# ESP-VINDRIKTNING_no_batt.net
KiCad netlist of a schematic drawn in EAGLE
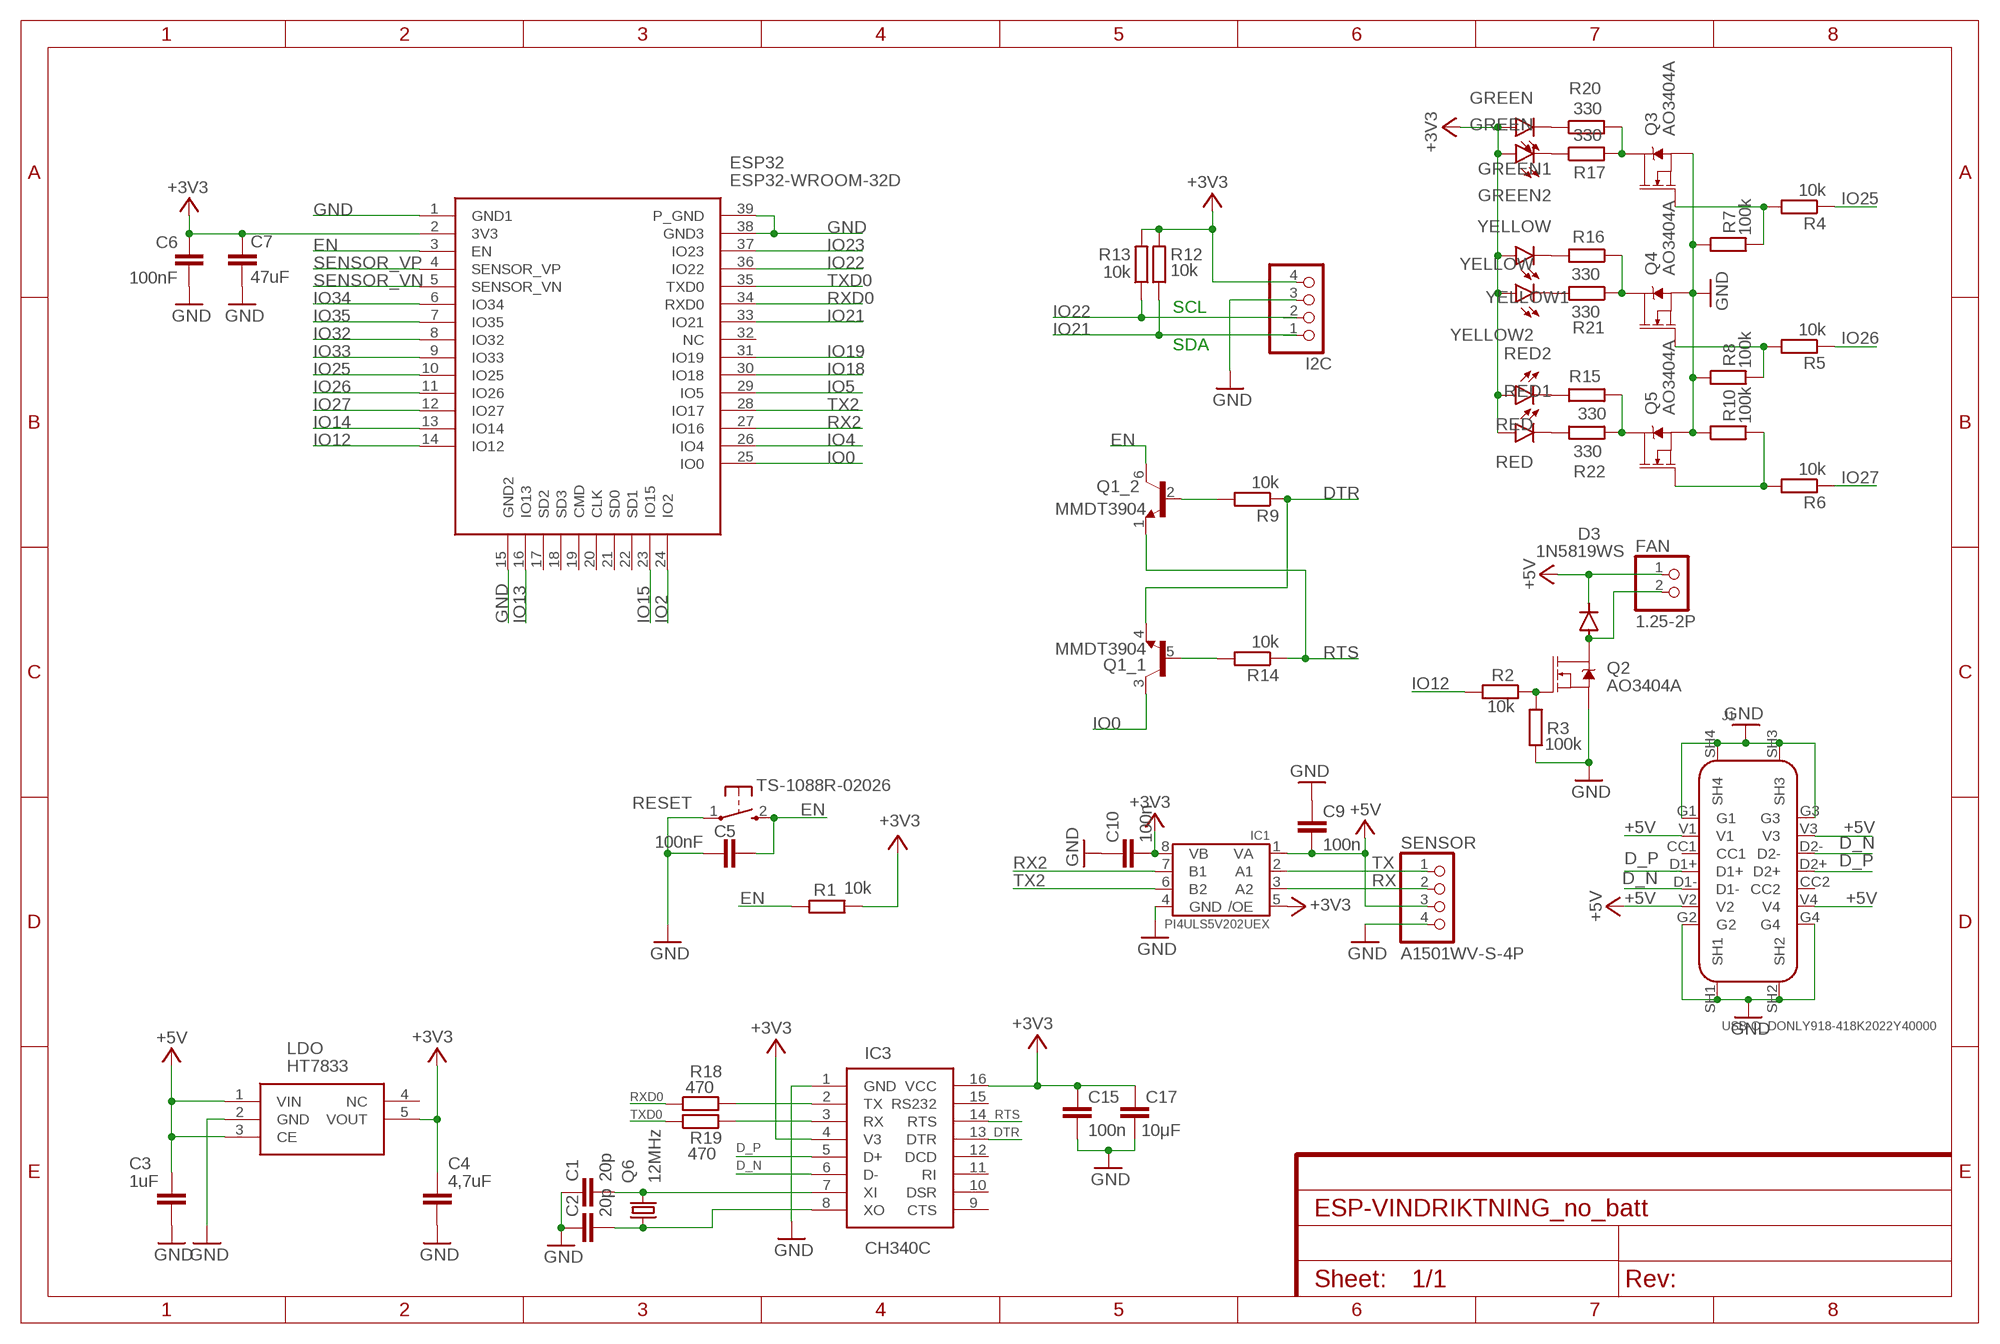
[diagram p0: schematic, sheet 1]

(export (version "E")
  (design (tool "Eeschema 10.0.6"))
  (components
    (comp (ref "C1")
      (value "20p")
      (footprint "eagle-import:C0402")
      (libsource (lib "eagle-import") (part "C-EUC0402"))
    )
    (comp (ref "C2")
      (value "20p")
      (footprint "eagle-import:C0402")
      (libsource (lib "eagle-import") (part "C-EUC0402"))
    )
    (comp (ref "C3")
      (value "1uF")
      (footprint "eagle-import:C0603")
      (libsource (lib "eagle-import") (part "C-EUC0603"))
    )
    (comp (ref "C4")
      (value "4,7uF")
      (footprint "eagle-import:C0603")
      (fields (field (name "LCSC_PART") "C19666"))
      (libsource (lib "eagle-import") (part "C-EUC0603"))
    )
    (comp (ref "C5")
      (value "100nF")
      (footprint "eagle-import:C0402")
      (libsource (lib "eagle-import") (part "C-EUC0402"))
    )
    (comp (ref "C6")
      (value "100nF")
      (footprint "eagle-import:C0603")
      (libsource (lib "eagle-import") (part "C-EUC0603"))
    )
    (comp (ref "C7")
      (value "47uF")
      (footprint "eagle-import:C0603")
      (fields (field (name "LCSC_PART") "C122913 "))
      (libsource (lib "eagle-import") (part "C-EUC0603"))
    )
    (comp (ref "C9")
      (value "100n")
      (footprint "eagle-import:C0603")
      (libsource (lib "eagle-import") (part "C-EUC0603"))
    )
    (comp (ref "C10")
      (value "100n")
      (footprint "eagle-import:C0603")
      (libsource (lib "eagle-import") (part "C-EUC0603"))
    )
    (comp (ref "C15")
      (value "100n")
      (footprint "eagle-import:C0603")
      (libsource (lib "eagle-import") (part "C-EUC0603"))
    )
    (comp (ref "C17")
      (value "10μF")
      (footprint "eagle-import:C0603")
      (libsource (lib "eagle-import") (part "C-EUC0603"))
    )
    (comp (ref "D3")
      (value "1N5819WS")
      (footprint "eagle-import:SOD323-R")
      (libsource (lib "eagle-import") (part "DIODE-SOD323-R"))
    )
    (comp (ref "ESP32")
      (value "ESP32-WROOM-32D")
      (footprint "eagle-import:ESP32WROOM32D")
      (fields (field (name "LCSC_PART") "C82899") (field (name "LCSC_PART_1") "C82899"))
      (libsource (lib "eagle-import") (part "ESP32-WROOM-32D"))
    )
    (comp (ref "FAN")
      (value "1.25-2P")
      (footprint "eagle-import:1.25-2P")
      (fields (field (name "LCSC_PART") "C393945"))
      (libsource (lib "eagle-import") (part "1.25-2P"))
    )
    (comp (ref "GREEN1")
      (value "GREEN")
      (footprint "eagle-import:CHIP-LED0603")
      (libsource (lib "eagle-import") (part "LEDCHIP-LED0603"))
    )
    (comp (ref "GREEN2")
      (value "GREEN")
      (footprint "eagle-import:CHIP-LED0603")
      (libsource (lib "eagle-import") (part "LEDCHIP-LED0603"))
    )
    (comp (ref "I2C")
      (value "PINHD-1X4")
      (footprint "eagle-import:1X04")
      (fields (field (name "LCSC_PART") "C2321"))
      (libsource (lib "eagle-import") (part "PINHD-1X4"))
    )
    (comp (ref "IC1")
      (value "PI4ULS5V202UEX")
      (footprint "eagle-import:MSOP8")
      (fields (field (name "LCSC_PART") "C481697"))
      (libsource (lib "eagle-import") (part "PI4ULS5V202UEX"))
    )
    (comp (ref "IC3")
      (value "CH340C")
      (footprint "eagle-import:SOIC16")
      (libsource (lib "eagle-import") (part "USB_UART_CONVERTOR_CH340G"))
    )
    (comp (ref "J1")
      (value "USB-C_DONLY918-418K2022Y40000")
      (footprint "eagle-import:USB-C-TH")
      (fields (field (name "LCSC_PART") "C168704"))
      (libsource (lib "eagle-import") (part "USB-C_DONLY918-418K2022Y40000"))
    )
    (comp (ref "LDO")
      (value "HT7833")
      (footprint "eagle-import:SOT23-5")
      (libsource (lib "eagle-import") (part "HT78XX-SOT23-5SOT23-5"))
    )
    (comp (ref "Q1")
      (value "MMDT3904")
      (footprint "eagle-import:SC70-6")
      (fields (field (name "LCSC_PART") "C268586"))
      (libsource (lib "eagle-import") (part "TRANS_NPN_DUAL-MBT3904DW1T1"))
    )
    (comp (ref "Q2")
      (value "AO3404A")
      (footprint "eagle-import:SOT23-3")
      (libsource (lib "eagle-import") (part "MOSFET-NCH-AO3404A"))
    )
    (comp (ref "Q3")
      (value "AO3404A")
      (footprint "eagle-import:SOT23-3")
      (libsource (lib "eagle-import") (part "MOSFET-NCH-AO3404A"))
    )
    (comp (ref "Q4")
      (value "AO3404A")
      (footprint "eagle-import:SOT23-3")
      (libsource (lib "eagle-import") (part "MOSFET-NCH-AO3404A"))
    )
    (comp (ref "Q5")
      (value "AO3404A")
      (footprint "eagle-import:SOT23-3")
      (libsource (lib "eagle-import") (part "MOSFET-NCH-AO3404A"))
    )
    (comp (ref "Q6")
      (value "12MHz")
      (footprint "eagle-import:3.2X2.5_KX-7")
      (fields (field (name "LCSC_PART") "C97242"))
      (libsource (lib "eagle-import") (part "KX-7"))
    )
    (comp (ref "R1")
      (value "10k")
      (footprint "eagle-import:R0402")
      (libsource (lib "eagle-import") (part "R-EU_R0402"))
    )
    (comp (ref "R2")
      (value "10k")
      (footprint "eagle-import:R0402")
      (libsource (lib "eagle-import") (part "R-EU_R0402"))
    )
    (comp (ref "R3")
      (value "100k")
      (footprint "eagle-import:R0402")
      (libsource (lib "eagle-import") (part "R-EU_R0402"))
    )
    (comp (ref "R4")
      (value "10k")
      (footprint "eagle-import:R0402")
      (libsource (lib "eagle-import") (part "R-EU_R0402"))
    )
    (comp (ref "R5")
      (value "10k")
      (footprint "eagle-import:R0402")
      (libsource (lib "eagle-import") (part "R-EU_R0402"))
    )
    (comp (ref "R6")
      (value "10k")
      (footprint "eagle-import:R0402")
      (libsource (lib "eagle-import") (part "R-EU_R0402"))
    )
    (comp (ref "R7")
      (value "100k")
      (footprint "eagle-import:R0402")
      (libsource (lib "eagle-import") (part "R-EU_R0402"))
    )
    (comp (ref "R8")
      (value "100k")
      (footprint "eagle-import:R0402")
      (libsource (lib "eagle-import") (part "R-EU_R0402"))
    )
    (comp (ref "R9")
      (value "10k")
      (footprint "eagle-import:R0402")
      (libsource (lib "eagle-import") (part "R-EU_R0402"))
    )
    (comp (ref "R10")
      (value "100k")
      (footprint "eagle-import:R0402")
      (libsource (lib "eagle-import") (part "R-EU_R0402"))
    )
    (comp (ref "R12")
      (value "10k")
      (footprint "eagle-import:R0603")
      (libsource (lib "eagle-import") (part "R-EU_R0603"))
    )
    (comp (ref "R13")
      (value "10k")
      (footprint "eagle-import:R0603")
      (libsource (lib "eagle-import") (part "R-EU_R0603"))
    )
    (comp (ref "R14")
      (value "10k")
      (footprint "eagle-import:R0402")
      (libsource (lib "eagle-import") (part "R-EU_R0402"))
    )
    (comp (ref "R15")
      (value "330")
      (footprint "eagle-import:R0603")
      (libsource (lib "eagle-import") (part "R-EU_R0603"))
    )
    (comp (ref "R16")
      (value "330")
      (footprint "eagle-import:R0603")
      (libsource (lib "eagle-import") (part "R-EU_R0603"))
    )
    (comp (ref "R17")
      (value "330")
      (footprint "eagle-import:R0603")
      (libsource (lib "eagle-import") (part "R-EU_R0603"))
    )
    (comp (ref "R18")
      (value "470")
      (footprint "eagle-import:R0402")
      (libsource (lib "eagle-import") (part "R-EU_R0402"))
    )
    (comp (ref "R19")
      (value "470")
      (footprint "eagle-import:R0402")
      (libsource (lib "eagle-import") (part "R-EU_R0402"))
    )
    (comp (ref "R20")
      (value "330")
      (footprint "eagle-import:R0603")
      (libsource (lib "eagle-import") (part "R-EU_R0603"))
    )
    (comp (ref "R21")
      (value "330")
      (footprint "eagle-import:R0603")
      (libsource (lib "eagle-import") (part "R-EU_R0603"))
    )
    (comp (ref "R22")
      (value "330")
      (footprint "eagle-import:R0603")
      (libsource (lib "eagle-import") (part "R-EU_R0603"))
    )
    (comp (ref "RED1")
      (value "RED")
      (footprint "eagle-import:CHIP-LED0603")
      (libsource (lib "eagle-import") (part "LEDCHIP-LED0603"))
    )
    (comp (ref "RED2")
      (value "RED")
      (footprint "eagle-import:CHIP-LED0603")
      (libsource (lib "eagle-import") (part "LEDCHIP-LED0603"))
    )
    (comp (ref "RESET")
      (value "TS-1088R-02026")
      (footprint "eagle-import:TS1088R02026")
      (libsource (lib "eagle-import") (part "MOMENTARY_SWITCH_TS-1088R-02026"))
    )
    (comp (ref "SENSOR")
      (value "A1501WV-S-4P")
      (footprint "eagle-import:A1501WV-S-4P")
      (fields (field (name "LCSC_PART") "C225162"))
      (libsource (lib "eagle-import") (part "A1501WV-S-4P"))
    )
    (comp (ref "YELLOW1")
      (value "YELLOW")
      (footprint "eagle-import:CHIP-LED0603")
      (libsource (lib "eagle-import") (part "LEDCHIP-LED0603"))
    )
    (comp (ref "YELLOW2")
      (value "YELLOW")
      (footprint "eagle-import:CHIP-LED0603")
      (libsource (lib "eagle-import") (part "LEDCHIP-LED0603"))
    )
  )
  (nets
    (net (code "1") (name "+3V3") (class "Default")
      (node (ref "C10") (pin "2") (pinfunction "2_2") (pintype "passive"))
      (node (ref "C15") (pin "1") (pinfunction "1_1") (pintype "passive"))
      (node (ref "C17") (pin "1") (pinfunction "1_1") (pintype "passive"))
      (node (ref "C4") (pin "1") (pinfunction "1_1") (pintype "passive"))
      (node (ref "C6") (pin "1") (pinfunction "1_1") (pintype "passive"))
      (node (ref "C7") (pin "1") (pinfunction "1_1") (pintype "passive"))
      (node (ref "ESP32") (pin "2") (pinfunction "3V3_2") (pintype "bidirectional"))
      (node (ref "GREEN1") (pin "A") (pinfunction "A_A") (pintype "passive"))
      (node (ref "GREEN2") (pin "A") (pinfunction "A_A") (pintype "passive"))
      (node (ref "I2C") (pin "4") (pinfunction "4_4") (pintype "passive"))
      (node (ref "IC1") (pin "5") (pinfunction "/OE_5") (pintype "bidirectional"))
      (node (ref "IC1") (pin "8") (pinfunction "VB_8") (pintype "bidirectional"))
      (node (ref "IC3") (pin "16") (pinfunction "VCC_16") (pintype "bidirectional"))
      (node (ref "IC3") (pin "4") (pinfunction "V3_4") (pintype "bidirectional"))
      (node (ref "LDO") (pin "5") (pinfunction "VOUT_5") (pintype "bidirectional"))
      (node (ref "R1") (pin "1") (pinfunction "1_1") (pintype "passive"))
      (node (ref "R12") (pin "2") (pinfunction "2_2") (pintype "passive"))
      (node (ref "R13") (pin "2") (pinfunction "2_2") (pintype "passive"))
      (node (ref "RED1") (pin "A") (pinfunction "A_A") (pintype "passive"))
      (node (ref "RED2") (pin "A") (pinfunction "A_A") (pintype "passive"))
      (node (ref "YELLOW1") (pin "A") (pinfunction "A_A") (pintype "passive"))
      (node (ref "YELLOW2") (pin "A") (pinfunction "A_A") (pintype "passive"))
    )
    (net (code "2") (name "+5V") (class "Default")
      (node (ref "C3") (pin "1") (pinfunction "1_1") (pintype "passive"))
      (node (ref "C9") (pin "2") (pinfunction "2_2") (pintype "passive"))
      (node (ref "D3") (pin "C") (pinfunction "C_C") (pintype "passive"))
      (node (ref "FAN") (pin "1") (pinfunction "1_1") (pintype "passive"))
      (node (ref "IC1") (pin "1") (pinfunction "VA_1") (pintype "bidirectional"))
      (node (ref "J1") (pin "V1") (pinfunction "V1_V1") (pintype "bidirectional"))
      (node (ref "J1") (pin "V2") (pinfunction "V2_V2") (pintype "bidirectional"))
      (node (ref "J1") (pin "V3") (pinfunction "V3_V3") (pintype "bidirectional"))
      (node (ref "J1") (pin "V4") (pinfunction "V4_V4") (pintype "bidirectional"))
      (node (ref "LDO") (pin "1") (pinfunction "VIN_1") (pintype "bidirectional"))
      (node (ref "LDO") (pin "3") (pinfunction "CE_3") (pintype "bidirectional"))
      (node (ref "SENSOR") (pin "3") (pinfunction "3_3") (pintype "passive"))
    )
    (net (code "3") (name "/DTR") (class "Default")
      (node (ref "IC3") (pin "13") (pinfunction "DTR_13") (pintype "bidirectional"))
      (node (ref "Q1") (pin "4") (pinfunction "E_4") (pintype "passive"))
      (node (ref "R9") (pin "1") (pinfunction "1_1") (pintype "passive"))
    )
    (net (code "4") (name "/D_N") (class "Default")
      (node (ref "IC3") (pin "6") (pinfunction "D-_6") (pintype "bidirectional"))
      (node (ref "J1") (pin "D1-") (pinfunction "D1-_D1-") (pintype "bidirectional"))
      (node (ref "J1") (pin "D2-") (pinfunction "D2-_D2-") (pintype "bidirectional"))
    )
    (net (code "5") (name "/D_P") (class "Default")
      (node (ref "IC3") (pin "5") (pinfunction "D+_5") (pintype "bidirectional"))
      (node (ref "J1") (pin "D1+") (pinfunction "D1+_D1+") (pintype "bidirectional"))
      (node (ref "J1") (pin "D2+") (pinfunction "D2+_D2+") (pintype "bidirectional"))
    )
    (net (code "6") (name "/EN") (class "Default")
      (node (ref "C5") (pin "2") (pinfunction "2_2") (pintype "passive"))
      (node (ref "ESP32") (pin "3") (pinfunction "EN_3") (pintype "bidirectional"))
      (node (ref "Q1") (pin "6") (pinfunction "C_6") (pintype "passive"))
      (node (ref "R1") (pin "2") (pinfunction "2_2") (pintype "passive"))
      (node (ref "RESET") (pin "2") (pinfunction "3_2") (pintype "passive"))
    )
    (net (code "7") (name "/IO0") (class "Default")
      (node (ref "ESP32") (pin "25") (pinfunction "IO0_25") (pintype "bidirectional"))
      (node (ref "Q1") (pin "3") (pinfunction "C_3") (pintype "passive"))
    )
    (net (code "8") (name "/IO2") (class "Default")
      (node (ref "ESP32") (pin "24") (pinfunction "IO2_24") (pintype "bidirectional"))
    )
    (net (code "9") (name "/IO4") (class "Default")
      (node (ref "ESP32") (pin "26") (pinfunction "IO4_26") (pintype "bidirectional"))
    )
    (net (code "10") (name "/IO5") (class "Default")
      (node (ref "ESP32") (pin "29") (pinfunction "IO5_29") (pintype "bidirectional"))
    )
    (net (code "11") (name "/IO12") (class "Default")
      (node (ref "ESP32") (pin "14") (pinfunction "IO12_14") (pintype "bidirectional"))
      (node (ref "R2") (pin "2") (pinfunction "2_2") (pintype "passive"))
    )
    (net (code "12") (name "/IO13") (class "Default")
      (node (ref "ESP32") (pin "16") (pinfunction "IO13_16") (pintype "bidirectional"))
    )
    (net (code "13") (name "/IO14") (class "Default")
      (node (ref "ESP32") (pin "13") (pinfunction "IO14_13") (pintype "bidirectional"))
    )
    (net (code "14") (name "/IO15") (class "Default")
      (node (ref "ESP32") (pin "23") (pinfunction "IO15_23") (pintype "bidirectional"))
    )
    (net (code "15") (name "/IO18") (class "Default")
      (node (ref "ESP32") (pin "30") (pinfunction "IO18_30") (pintype "bidirectional"))
    )
    (net (code "16") (name "/IO19") (class "Default")
      (node (ref "ESP32") (pin "31") (pinfunction "IO19_31") (pintype "bidirectional"))
    )
    (net (code "17") (name "/IO21") (class "Default")
      (node (ref "ESP32") (pin "33") (pinfunction "IO21_33") (pintype "bidirectional"))
      (node (ref "I2C") (pin "1") (pinfunction "1_1") (pintype "passive"))
      (node (ref "R12") (pin "1") (pinfunction "1_1") (pintype "passive"))
    )
    (net (code "18") (name "/IO22") (class "Default")
      (node (ref "ESP32") (pin "36") (pinfunction "IO22_36") (pintype "bidirectional"))
      (node (ref "I2C") (pin "2") (pinfunction "2_2") (pintype "passive"))
      (node (ref "R13") (pin "1") (pinfunction "1_1") (pintype "passive"))
    )
    (net (code "19") (name "/IO23") (class "Default")
      (node (ref "ESP32") (pin "37") (pinfunction "IO23_37") (pintype "bidirectional"))
    )
    (net (code "20") (name "/IO25") (class "Default")
      (node (ref "ESP32") (pin "10") (pinfunction "IO25_10") (pintype "bidirectional"))
      (node (ref "R4") (pin "1") (pinfunction "1_1") (pintype "passive"))
    )
    (net (code "21") (name "/IO26") (class "Default")
      (node (ref "ESP32") (pin "11") (pinfunction "IO26_11") (pintype "bidirectional"))
      (node (ref "R5") (pin "1") (pinfunction "1_1") (pintype "passive"))
    )
    (net (code "22") (name "/IO27") (class "Default")
      (node (ref "ESP32") (pin "12") (pinfunction "IO27_12") (pintype "bidirectional"))
      (node (ref "R6") (pin "1") (pinfunction "1_1") (pintype "passive"))
    )
    (net (code "23") (name "/IO32") (class "Default")
      (node (ref "ESP32") (pin "8") (pinfunction "IO32_8") (pintype "bidirectional"))
    )
    (net (code "24") (name "/IO33") (class "Default")
      (node (ref "ESP32") (pin "9") (pinfunction "IO33_9") (pintype "bidirectional"))
    )
    (net (code "25") (name "/IO34") (class "Default")
      (node (ref "ESP32") (pin "6") (pinfunction "IO34_6") (pintype "bidirectional"))
    )
    (net (code "26") (name "/IO35") (class "Default")
      (node (ref "ESP32") (pin "7") (pinfunction "IO35_7") (pintype "bidirectional"))
    )
    (net (code "27") (name "/RTS") (class "Default")
      (node (ref "IC3") (pin "14") (pinfunction "RTS_14") (pintype "bidirectional"))
      (node (ref "Q1") (pin "1") (pinfunction "E_1") (pintype "passive"))
      (node (ref "R14") (pin "1") (pinfunction "1_1") (pintype "passive"))
    )
    (net (code "28") (name "/RX") (class "Default")
      (node (ref "IC1") (pin "3") (pinfunction "A2_3") (pintype "bidirectional"))
      (node (ref "SENSOR") (pin "2") (pinfunction "2_2") (pintype "passive"))
    )
    (net (code "29") (name "/RX2") (class "Default")
      (node (ref "ESP32") (pin "27") (pinfunction "IO16_27") (pintype "bidirectional"))
      (node (ref "IC1") (pin "7") (pinfunction "B1_7") (pintype "bidirectional"))
    )
    (net (code "30") (name "/RXD0") (class "Default")
      (node (ref "ESP32") (pin "34") (pinfunction "RXD0_34") (pintype "bidirectional"))
      (node (ref "R18") (pin "1") (pinfunction "1_1") (pintype "passive"))
    )
    (net (code "31") (name "/SENSOR_VN") (class "Default")
      (node (ref "ESP32") (pin "5") (pinfunction "SENSOR_VN_5") (pintype "bidirectional"))
    )
    (net (code "32") (name "/SENSOR_VP") (class "Default")
      (node (ref "ESP32") (pin "4") (pinfunction "SENSOR_VP_4") (pintype "bidirectional"))
    )
    (net (code "33") (name "/TX") (class "Default")
      (node (ref "IC1") (pin "2") (pinfunction "A1_2") (pintype "bidirectional"))
      (node (ref "SENSOR") (pin "1") (pinfunction "1_1") (pintype "passive"))
    )
    (net (code "34") (name "/TX2") (class "Default")
      (node (ref "ESP32") (pin "28") (pinfunction "IO17_28") (pintype "bidirectional"))
      (node (ref "IC1") (pin "6") (pinfunction "B2_6") (pintype "bidirectional"))
    )
    (net (code "35") (name "/TXD0") (class "Default")
      (node (ref "ESP32") (pin "35") (pinfunction "TXD0_35") (pintype "bidirectional"))
      (node (ref "R19") (pin "1") (pinfunction "1_1") (pintype "passive"))
    )
    (net (code "36") (name "GND") (class "Default")
      (node (ref "C1") (pin "1") (pinfunction "1_1") (pintype "passive"))
      (node (ref "C10") (pin "1") (pinfunction "1_1") (pintype "passive"))
      (node (ref "C15") (pin "2") (pinfunction "2_2") (pintype "passive"))
      (node (ref "C17") (pin "2") (pinfunction "2_2") (pintype "passive"))
      (node (ref "C2") (pin "1") (pinfunction "1_1") (pintype "passive"))
      (node (ref "C3") (pin "2") (pinfunction "2_2") (pintype "passive"))
      (node (ref "C4") (pin "2") (pinfunction "2_2") (pintype "passive"))
      (node (ref "C5") (pin "1") (pinfunction "1_1") (pintype "passive"))
      (node (ref "C6") (pin "2") (pinfunction "2_2") (pintype "passive"))
      (node (ref "C7") (pin "2") (pinfunction "2_2") (pintype "passive"))
      (node (ref "C9") (pin "1") (pinfunction "1_1") (pintype "passive"))
      (node (ref "ESP32") (pin "1") (pinfunction "GND1_1") (pintype "bidirectional"))
      (node (ref "ESP32") (pin "15") (pinfunction "GND2_15") (pintype "bidirectional"))
      (node (ref "ESP32") (pin "38") (pinfunction "GND3_38") (pintype "bidirectional"))
      (node (ref "ESP32") (pin "39") (pinfunction "P_GND_39") (pintype "bidirectional"))
      (node (ref "I2C") (pin "3") (pinfunction "3_3") (pintype "passive"))
      (node (ref "IC1") (pin "4") (pinfunction "GND_4") (pintype "bidirectional"))
      (node (ref "IC3") (pin "1") (pinfunction "GND_1") (pintype "bidirectional"))
      (node (ref "J1") (pin "G1") (pinfunction "G1_G1") (pintype "bidirectional"))
      (node (ref "J1") (pin "G2") (pinfunction "G2_G2") (pintype "bidirectional"))
      (node (ref "J1") (pin "G3") (pinfunction "G3_G3") (pintype "bidirectional"))
      (node (ref "J1") (pin "G4") (pinfunction "G4_G4") (pintype "bidirectional"))
      (node (ref "J1") (pin "SH1") (pinfunction "SH1_SH1") (pintype "bidirectional"))
      (node (ref "J1") (pin "SH2") (pinfunction "SH2_SH2") (pintype "bidirectional"))
      (node (ref "J1") (pin "SH3") (pinfunction "SH3_SH3") (pintype "bidirectional"))
      (node (ref "J1") (pin "SH4") (pinfunction "SH4_SH4") (pintype "bidirectional"))
      (node (ref "LDO") (pin "2") (pinfunction "GND_2") (pintype "bidirectional"))
      (node (ref "Q2") (pin "2") (pinfunction "S_2") (pintype "bidirectional"))
      (node (ref "Q3") (pin "2") (pinfunction "S_2") (pintype "bidirectional"))
      (node (ref "Q4") (pin "2") (pinfunction "S_2") (pintype "bidirectional"))
      (node (ref "Q5") (pin "2") (pinfunction "S_2") (pintype "bidirectional"))
      (node (ref "R10") (pin "1") (pinfunction "1_1") (pintype "passive"))
      (node (ref "R3") (pin "2") (pinfunction "2_2") (pintype "passive"))
      (node (ref "R7") (pin "1") (pinfunction "1_1") (pintype "passive"))
      (node (ref "R8") (pin "1") (pinfunction "1_1") (pintype "passive"))
      (node (ref "RESET") (pin "1") (pinfunction "1_1") (pintype "passive"))
      (node (ref "SENSOR") (pin "4") (pinfunction "4_4") (pintype "passive"))
    )
    (net (code "37") (name "Net-(GREEN1-PadC)") (class "Default")
      (node (ref "GREEN1") (pin "C") (pinfunction "C_C") (pintype "passive"))
      (node (ref "R20") (pin "1") (pinfunction "1_1") (pintype "passive"))
    )
    (net (code "38") (name "Net-(GREEN2-PadC)") (class "Default")
      (node (ref "GREEN2") (pin "C") (pinfunction "C_C") (pintype "passive"))
      (node (ref "R17") (pin "1") (pinfunction "1_1") (pintype "passive"))
    )
    (net (code "39") (name "Net-(IC3-RX)") (class "Default")
      (node (ref "IC3") (pin "3") (pinfunction "RX_3") (pintype "bidirectional"))
      (node (ref "R19") (pin "2") (pinfunction "2_2") (pintype "passive"))
    )
    (net (code "40") (name "Net-(IC3-TX)") (class "Default")
      (node (ref "IC3") (pin "2") (pinfunction "TX_2") (pintype "bidirectional"))
      (node (ref "R18") (pin "2") (pinfunction "2_2") (pintype "passive"))
    )
    (net (code "41") (name "Net-(IC3-XI)") (class "Default")
      (node (ref "C1") (pin "2") (pinfunction "2_2") (pintype "passive"))
      (node (ref "IC3") (pin "7") (pinfunction "XI_7") (pintype "bidirectional"))
      (node (ref "Q6") (pin "3") (pinfunction "2_3") (pintype "passive"))
    )
    (net (code "42") (name "Net-(IC3-XO)") (class "Default")
      (node (ref "C2") (pin "2") (pinfunction "2_2") (pintype "passive"))
      (node (ref "IC3") (pin "8") (pinfunction "XO_8") (pintype "bidirectional"))
      (node (ref "Q6") (pin "1") (pinfunction "1_1") (pintype "passive"))
    )
    (net (code "43") (name "Net-(Q1A-B)") (class "Default")
      (node (ref "Q1") (pin "5") (pinfunction "B_5") (pintype "passive"))
      (node (ref "R14") (pin "2") (pinfunction "2_2") (pintype "passive"))
    )
    (net (code "44") (name "Net-(Q1B-B)") (class "Default")
      (node (ref "Q1") (pin "2") (pinfunction "B_2") (pintype "passive"))
      (node (ref "R9") (pin "2") (pinfunction "2_2") (pintype "passive"))
    )
    (net (code "45") (name "Net-(Q2-D)") (class "Default")
      (node (ref "D3") (pin "A") (pinfunction "A_A") (pintype "passive"))
      (node (ref "FAN") (pin "2") (pinfunction "2_2") (pintype "passive"))
      (node (ref "Q2") (pin "3") (pinfunction "D_3") (pintype "bidirectional"))
    )
    (net (code "46") (name "Net-(Q2-G)") (class "Default")
      (node (ref "Q2") (pin "1") (pinfunction "G_1") (pintype "bidirectional"))
      (node (ref "R2") (pin "1") (pinfunction "1_1") (pintype "passive"))
      (node (ref "R3") (pin "1") (pinfunction "1_1") (pintype "passive"))
    )
    (net (code "47") (name "Net-(Q3-D)") (class "Default")
      (node (ref "Q3") (pin "3") (pinfunction "D_3") (pintype "bidirectional"))
      (node (ref "R17") (pin "2") (pinfunction "2_2") (pintype "passive"))
      (node (ref "R20") (pin "2") (pinfunction "2_2") (pintype "passive"))
    )
    (net (code "48") (name "Net-(Q3-G)") (class "Default")
      (node (ref "Q3") (pin "1") (pinfunction "G_1") (pintype "bidirectional"))
      (node (ref "R4") (pin "2") (pinfunction "2_2") (pintype "passive"))
      (node (ref "R7") (pin "2") (pinfunction "2_2") (pintype "passive"))
    )
    (net (code "49") (name "Net-(Q4-D)") (class "Default")
      (node (ref "Q4") (pin "3") (pinfunction "D_3") (pintype "bidirectional"))
      (node (ref "R16") (pin "1") (pinfunction "1_1") (pintype "passive"))
      (node (ref "R21") (pin "1") (pinfunction "1_1") (pintype "passive"))
    )
    (net (code "50") (name "Net-(Q4-G)") (class "Default")
      (node (ref "Q4") (pin "1") (pinfunction "G_1") (pintype "bidirectional"))
      (node (ref "R5") (pin "2") (pinfunction "2_2") (pintype "passive"))
      (node (ref "R8") (pin "2") (pinfunction "2_2") (pintype "passive"))
    )
    (net (code "51") (name "Net-(Q5-D)") (class "Default")
      (node (ref "Q5") (pin "3") (pinfunction "D_3") (pintype "bidirectional"))
      (node (ref "R15") (pin "2") (pinfunction "2_2") (pintype "passive"))
      (node (ref "R22") (pin "2") (pinfunction "2_2") (pintype "passive"))
    )
    (net (code "52") (name "Net-(Q5-G)") (class "Default")
      (node (ref "Q5") (pin "1") (pinfunction "G_1") (pintype "bidirectional"))
      (node (ref "R10") (pin "2") (pinfunction "2_2") (pintype "passive"))
      (node (ref "R6") (pin "2") (pinfunction "2_2") (pintype "passive"))
    )
    (net (code "53") (name "Net-(R15-Pad1)") (class "Default")
      (node (ref "R15") (pin "1") (pinfunction "1_1") (pintype "passive"))
      (node (ref "RED2") (pin "C") (pinfunction "C_C") (pintype "passive"))
    )
    (net (code "54") (name "Net-(R16-Pad2)") (class "Default")
      (node (ref "R16") (pin "2") (pinfunction "2_2") (pintype "passive"))
      (node (ref "YELLOW1") (pin "C") (pinfunction "C_C") (pintype "passive"))
    )
    (net (code "55") (name "Net-(R21-Pad2)") (class "Default")
      (node (ref "R21") (pin "2") (pinfunction "2_2") (pintype "passive"))
      (node (ref "YELLOW2") (pin "C") (pinfunction "C_C") (pintype "passive"))
    )
    (net (code "56") (name "Net-(R22-Pad1)") (class "Default")
      (node (ref "R22") (pin "1") (pinfunction "1_1") (pintype "passive"))
      (node (ref "RED1") (pin "C") (pinfunction "C_C") (pintype "passive"))
    )
    (net (code "57") (name "unconnected-(ESP32-CLK-Pad20)") (class "Default")
      (node (ref "ESP32") (pin "20") (pinfunction "CLK_20") (pintype "bidirectional"))
    )
    (net (code "58") (name "unconnected-(ESP32-CMD-Pad19)") (class "Default")
      (node (ref "ESP32") (pin "19") (pinfunction "CMD_19") (pintype "bidirectional"))
    )
    (net (code "59") (name "unconnected-(ESP32-NC-Pad32)") (class "Default")
      (node (ref "ESP32") (pin "32") (pinfunction "NC_32") (pintype "no_connect"))
    )
    (net (code "60") (name "unconnected-(ESP32-SD0-Pad21)") (class "Default")
      (node (ref "ESP32") (pin "21") (pinfunction "SD0_21") (pintype "bidirectional"))
    )
    (net (code "61") (name "unconnected-(ESP32-SD1-Pad22)") (class "Default")
      (node (ref "ESP32") (pin "22") (pinfunction "SD1_22") (pintype "bidirectional"))
    )
    (net (code "62") (name "unconnected-(ESP32-SD2-Pad17)") (class "Default")
      (node (ref "ESP32") (pin "17") (pinfunction "SD2_17") (pintype "bidirectional"))
    )
    (net (code "63") (name "unconnected-(ESP32-SD3-Pad18)") (class "Default")
      (node (ref "ESP32") (pin "18") (pinfunction "SD3_18") (pintype "bidirectional"))
    )
    (net (code "64") (name "unconnected-(IC3-CTS-Pad9)") (class "Default")
      (node (ref "IC3") (pin "9") (pinfunction "CTS_9") (pintype "bidirectional"))
    )
    (net (code "65") (name "unconnected-(IC3-DCD-Pad12)") (class "Default")
      (node (ref "IC3") (pin "12") (pinfunction "DCD_12") (pintype "bidirectional"))
    )
    (net (code "66") (name "unconnected-(IC3-DSR-Pad10)") (class "Default")
      (node (ref "IC3") (pin "10") (pinfunction "DSR_10") (pintype "bidirectional"))
    )
    (net (code "67") (name "unconnected-(IC3-RI-Pad11)") (class "Default")
      (node (ref "IC3") (pin "11") (pinfunction "RI_11") (pintype "bidirectional"))
    )
    (net (code "68") (name "unconnected-(IC3-RS232-Pad15)") (class "Default")
      (node (ref "IC3") (pin "15") (pinfunction "RS232_15") (pintype "bidirectional"))
    )
    (net (code "69") (name "unconnected-(J1-PadCC1)") (class "Default")
      (node (ref "J1") (pin "CC1") (pinfunction "CC1_CC1") (pintype "bidirectional"))
    )
    (net (code "70") (name "unconnected-(J1-PadCC2)") (class "Default")
      (node (ref "J1") (pin "CC2") (pinfunction "CC2_CC2") (pintype "bidirectional"))
    )
    (net (code "71") (name "unconnected-(LDO-NC-Pad4)") (class "Default")
      (node (ref "LDO") (pin "4") (pinfunction "NC_4") (pintype "no_connect"))
    )
  )
)
